# board_rfm95_v2.net
KiCad netlist of a schematic drawn in EAGLE
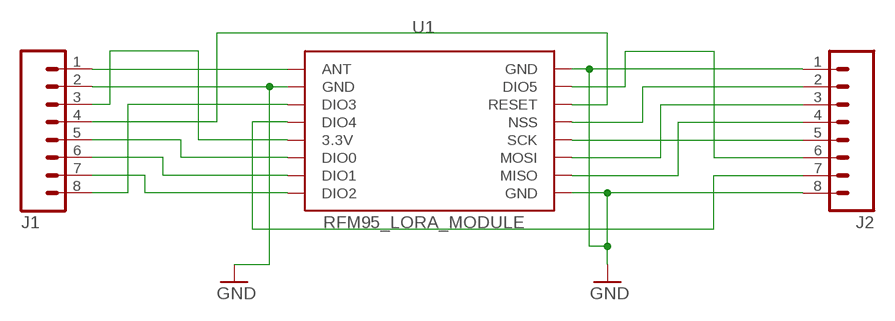
[diagram p0: schematic, sheet 1]

(export (version "E")
  (design (tool "Eeschema 10.0.6"))
  (components
    (comp (ref "J1")
      (value "M08")
      (footprint "eagle-import:1X08_ROUND")
      (libsource (lib "eagle-import") (part "M08"))
    )
    (comp (ref "J2")
      (value "M08")
      (footprint "eagle-import:1X08_ROUND")
      (libsource (lib "eagle-import") (part "M08"))
    )
    (comp (ref "U1")
      (value "RFM95_LORA_MODULE")
      (footprint "eagle-import:RFM95")
      (libsource (lib "eagle-import") (part "RFM95_LORA_MODULE"))
    )
  )
  (nets
    (net (code "1") (name "GND") (class "Default")
      (node (ref "J1") (pin "2") (pinfunction "2_2") (pintype "passive"))
      (node (ref "J2") (pin "1") (pinfunction "1_1") (pintype "passive"))
      (node (ref "J2") (pin "8") (pinfunction "8_8") (pintype "passive"))
      (node (ref "U1") (pin "GND") (pinfunction "GND_GND") (pintype "power_in"))
      (node (ref "U1") (pin "GND@1") (pinfunction "GND_GND@1") (pintype "power_in"))
      (node (ref "U1") (pin "GND@2") (pinfunction "GND_GND@2") (pintype "power_in"))
    )
    (net (code "2") (name "Net-(J1-Pad1)") (class "Default")
      (node (ref "J1") (pin "1") (pinfunction "1_1") (pintype "passive"))
      (node (ref "U1") (pin "ANT") (pinfunction "ANT_ANT") (pintype "power_in"))
    )
    (net (code "3") (name "Net-(J1-Pad3)") (class "Default")
      (node (ref "J1") (pin "3") (pinfunction "3_3") (pintype "passive"))
      (node (ref "U1") (pin "3.3V") (pinfunction "3.3V_3.3V") (pintype "bidirectional"))
    )
    (net (code "4") (name "Net-(J1-Pad4)") (class "Default")
      (node (ref "J1") (pin "4") (pinfunction "4_4") (pintype "passive"))
      (node (ref "U1") (pin "RESET") (pinfunction "RESET_RESET") (pintype "bidirectional"))
    )
    (net (code "5") (name "Net-(J1-Pad5)") (class "Default")
      (node (ref "J1") (pin "5") (pinfunction "5_5") (pintype "passive"))
      (node (ref "U1") (pin "DIO0") (pinfunction "DIO0_DIO0") (pintype "bidirectional"))
    )
    (net (code "6") (name "Net-(J1-Pad6)") (class "Default")
      (node (ref "J1") (pin "6") (pinfunction "6_6") (pintype "passive"))
      (node (ref "U1") (pin "DIO1") (pinfunction "DIO1_DIO1") (pintype "bidirectional"))
    )
    (net (code "7") (name "Net-(J1-Pad7)") (class "Default")
      (node (ref "J1") (pin "7") (pinfunction "7_7") (pintype "passive"))
      (node (ref "U1") (pin "DIO2") (pinfunction "DIO2_DIO2") (pintype "bidirectional"))
    )
    (net (code "8") (name "Net-(J1-Pad8)") (class "Default")
      (node (ref "J1") (pin "8") (pinfunction "8_8") (pintype "passive"))
      (node (ref "U1") (pin "DIO3") (pinfunction "DIO3_DIO3") (pintype "power_in"))
    )
    (net (code "9") (name "Net-(J2-Pad2)") (class "Default")
      (node (ref "J2") (pin "2") (pinfunction "2_2") (pintype "passive"))
      (node (ref "U1") (pin "NSS") (pinfunction "NSS_NSS") (pintype "bidirectional"))
    )
    (net (code "10") (name "Net-(J2-Pad3)") (class "Default")
      (node (ref "J2") (pin "3") (pinfunction "3_3") (pintype "passive"))
      (node (ref "U1") (pin "MOSI") (pinfunction "MOSI_MOSI") (pintype "bidirectional"))
    )
    (net (code "11") (name "Net-(J2-Pad4)") (class "Default")
      (node (ref "J2") (pin "4") (pinfunction "4_4") (pintype "passive"))
      (node (ref "U1") (pin "MISO") (pinfunction "MISO_MISO") (pintype "bidirectional"))
    )
    (net (code "12") (name "Net-(J2-Pad5)") (class "Default")
      (node (ref "J2") (pin "5") (pinfunction "5_5") (pintype "passive"))
      (node (ref "U1") (pin "SCK") (pinfunction "SCK_SCK") (pintype "bidirectional"))
    )
    (net (code "13") (name "Net-(J2-Pad6)") (class "Default")
      (node (ref "J2") (pin "6") (pinfunction "6_6") (pintype "passive"))
      (node (ref "U1") (pin "DIO5") (pinfunction "DIO5_DIO5") (pintype "bidirectional"))
    )
    (net (code "14") (name "Net-(J2-Pad7)") (class "Default")
      (node (ref "J2") (pin "7") (pinfunction "7_7") (pintype "passive"))
      (node (ref "U1") (pin "DIO4") (pinfunction "DIO4_DIO4") (pintype "bidirectional"))
    )
  )
)
